# Simple-Transmitter-2N918.net
KiCad netlist of a schematic drawn in EAGLE
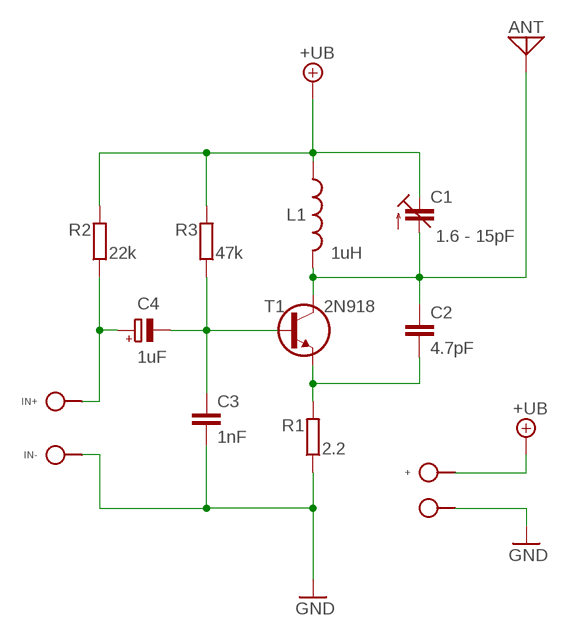
[diagram p0: schematic, sheet 1]

(export (version "E")
  (design (tool "Eeschema 10.0.6"))
  (components
    (comp (ref "+")
      (value "SPAD")
      (footprint "eagle-import:SPAD")
      (libsource (lib "eagle-import") (part "SPAD"))
    )
    (comp (ref "ANT")
      (value "ANT")
      (footprint "eagle-import:SPAD")
      (libsource (lib "eagle-import") (part "ANT"))
    )
    (comp (ref "C1")
      (value "1.6 - 15pF")
      (footprint "eagle-import:TRIM-2222-808")
      (libsource (lib "eagle-import") (part "C-TR-PH201272222-808-2PINB"))
    )
    (comp (ref "C2")
      (value "4.7pF")
      (footprint "eagle-import:C025-020X036")
      (libsource (lib "eagle-import") (part "C025-020X036"))
    )
    (comp (ref "C3")
      (value "1nF")
      (footprint "eagle-import:C025-020X036")
      (libsource (lib "eagle-import") (part "C025-020X036"))
    )
    (comp (ref "C4")
      (value "1uF")
      (footprint "eagle-import:E2,5-3")
      (libsource (lib "eagle-import") (part "CPOLE2,5-3"))
    )
    (comp (ref "IN+")
      (value "SPAD")
      (footprint "eagle-import:SPAD")
      (libsource (lib "eagle-import") (part "SPAD"))
    )
    (comp (ref "IN-")
      (value "SPAD")
      (footprint "eagle-import:SPAD")
      (libsource (lib "eagle-import") (part "SPAD"))
    )
    (comp (ref "L1")
      (value "1uH")
      (footprint "eagle-import:L-04_7")
      (libsource (lib "eagle-import") (part "L04/7"))
    )
    (comp (ref "R1")
      (value "2.2")
      (footprint "eagle-import:0202V")
      (libsource (lib "eagle-import") (part "R0202V"))
    )
    (comp (ref "R2")
      (value "22k")
      (footprint "eagle-import:0202_5")
      (libsource (lib "eagle-import") (part "R0202/5"))
    )
    (comp (ref "R3")
      (value "47k")
      (footprint "eagle-import:0202_5")
      (libsource (lib "eagle-import") (part "R0202/5"))
    )
    (comp (ref "T1")
      (value "2N918")
      (footprint "eagle-import:TO-72")
      (libsource (lib "eagle-import") (part "2N918TO-72-CE"))
    )
    (comp (ref "̶̶")
      (value "SPAD")
      (footprint "eagle-import:SPAD")
      (libsource (lib "eagle-import") (part "SPAD"))
    )
  )
  (nets
    (net (code "1") (name "+UB") (class "Default")
      (node (ref "+") (pin "1") (pinfunction "P$1_1") (pintype "bidirectional"))
      (node (ref "C1") (pin "3") (pinfunction "A_3") (pintype "passive"))
      (node (ref "L1") (pin "1") (pinfunction "1_1") (pintype "passive"))
      (node (ref "R2") (pin "2") (pinfunction "2_2") (pintype "passive"))
      (node (ref "R3") (pin "2") (pinfunction "2_2") (pintype "passive"))
    )
    (net (code "2") (name "GND") (class "Default")
      (node (ref "C3") (pin "2") (pinfunction "2_2") (pintype "passive"))
      (node (ref "IN-") (pin "1") (pinfunction "P$1_1") (pintype "bidirectional"))
      (node (ref "R1") (pin "1") (pinfunction "1_1") (pintype "passive"))
      (node (ref "̶̶") (pin "1") (pinfunction "P$1_1") (pintype "bidirectional"))
    )
    (net (code "3") (name "Net-(C1-E)") (class "Default")
      (node (ref "ANT") (pin "1") (pinfunction "1_1") (pintype "output"))
      (node (ref "C1") (pin "2") (pinfunction "E_2") (pintype "passive"))
      (node (ref "C2") (pin "1") (pinfunction "1_1") (pintype "passive"))
      (node (ref "L1") (pin "2") (pinfunction "2_2") (pintype "passive"))
      (node (ref "T1") (pin "3") (pinfunction "C_3") (pintype "passive"))
    )
    (net (code "4") (name "Net-(C2-Pad2)") (class "Default")
      (node (ref "C2") (pin "2") (pinfunction "2_2") (pintype "passive"))
      (node (ref "R1") (pin "2") (pinfunction "2_2") (pintype "passive"))
      (node (ref "T1") (pin "1") (pinfunction "E_1") (pintype "passive"))
      (node (ref "T1") (pin "4") (pinfunction "E_4") (pintype "passive"))
    )
    (net (code "5") (name "Net-(IN+-P$1)") (class "Default")
      (node (ref "C4") (pin "+") (pinfunction "+_+") (pintype "passive"))
      (node (ref "IN+") (pin "1") (pinfunction "P$1_1") (pintype "bidirectional"))
      (node (ref "R2") (pin "1") (pinfunction "1_1") (pintype "passive"))
    )
    (net (code "6") (name "Net-(T1-B)") (class "Default")
      (node (ref "C3") (pin "1") (pinfunction "1_1") (pintype "passive"))
      (node (ref "C4") (pin "-") (pinfunction "-_-") (pintype "passive"))
      (node (ref "R3") (pin "1") (pinfunction "1_1") (pintype "passive"))
      (node (ref "T1") (pin "2") (pinfunction "B_2") (pintype "passive"))
    )
  )
)
